# led_matrix.net
KiCad netlist of a schematic drawn in EAGLE
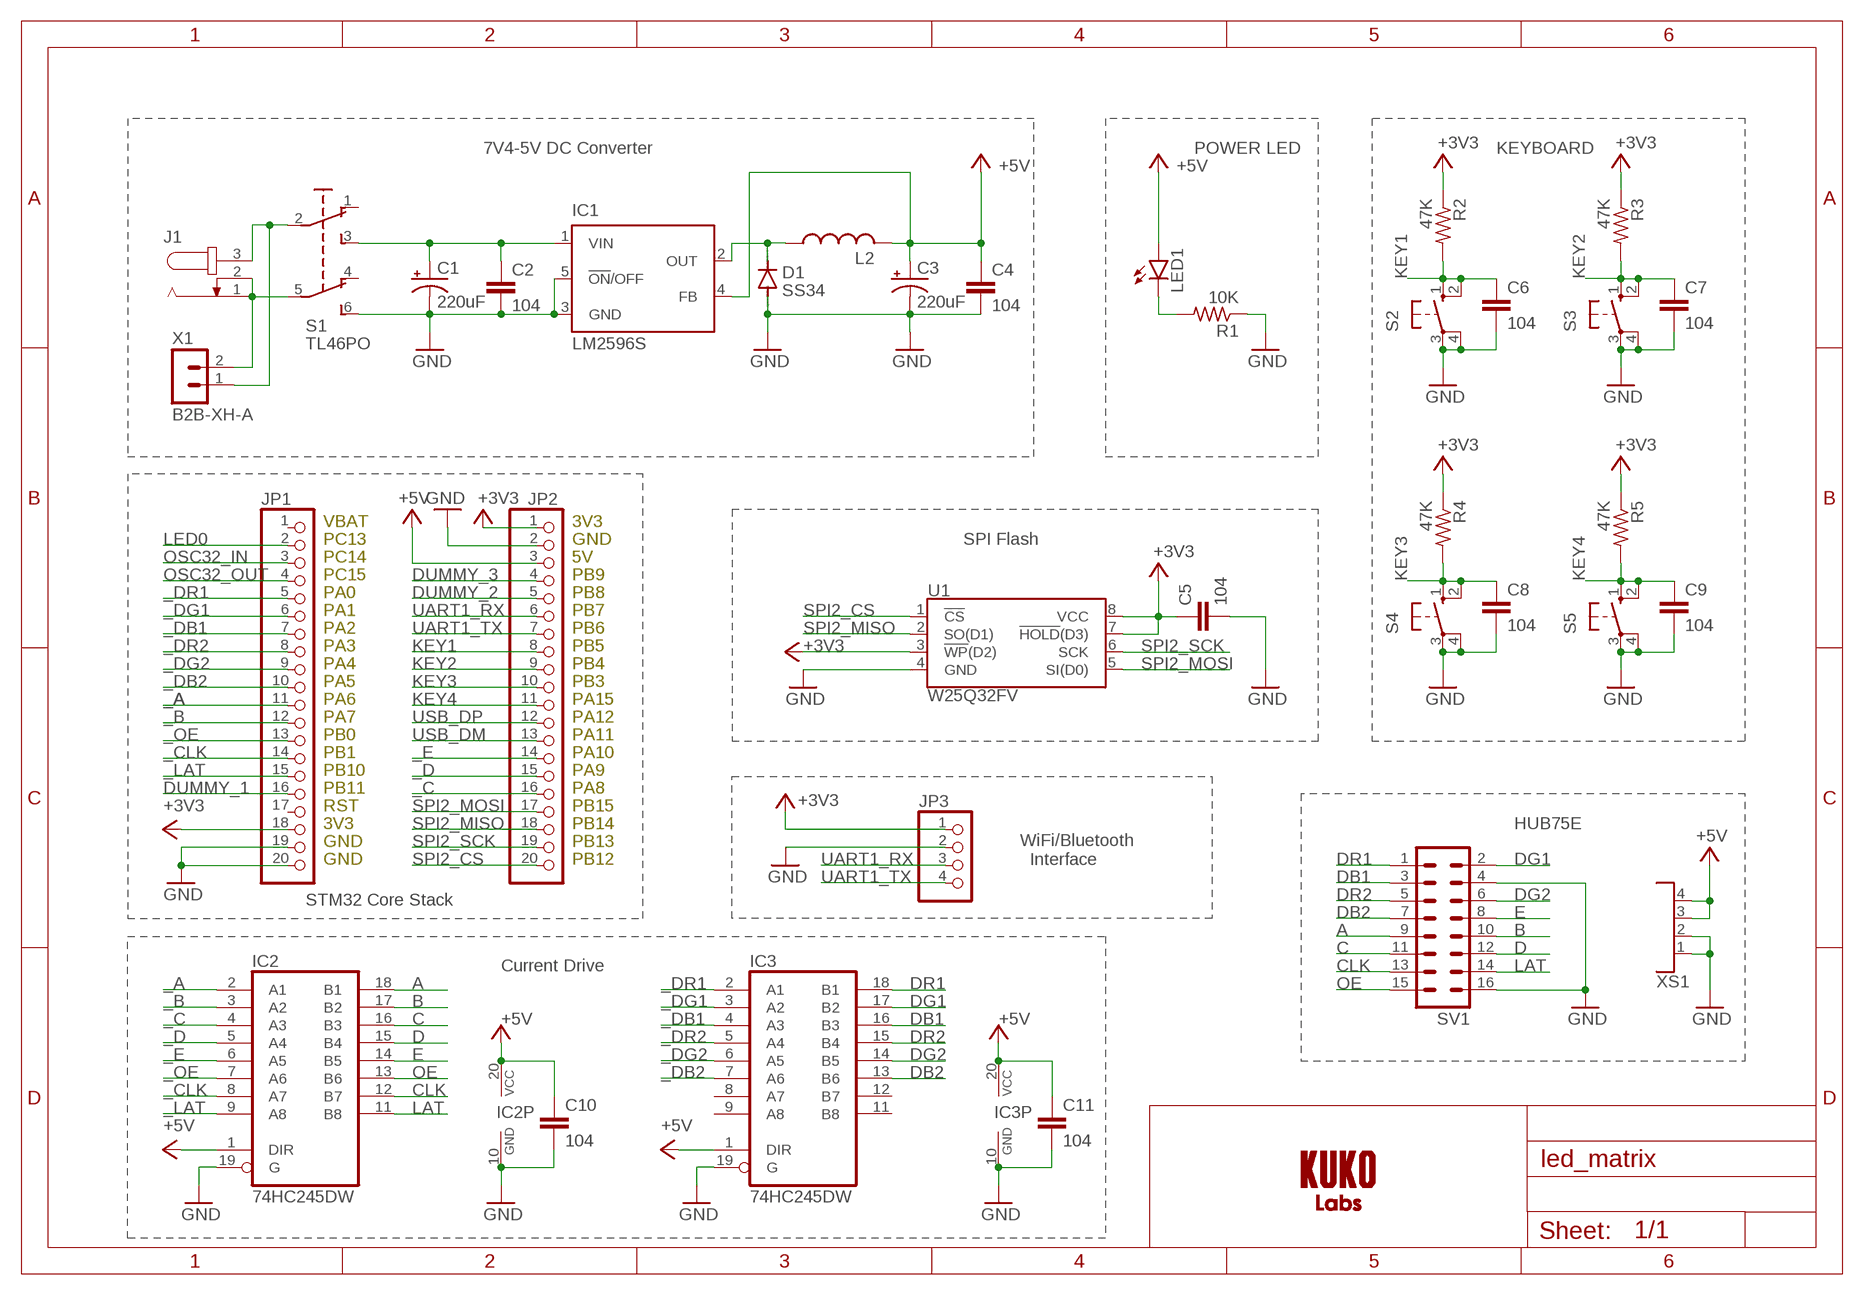
[diagram p0: schematic, sheet 1]

(export (version "E")
  (design (tool "Eeschema 10.0.6"))
  (components
    (comp (ref "C1")
      (value "220uF")
      (footprint "eagle-import:153CLV-0605")
      (libsource (lib "eagle-import") (part "CPOL-US153CLV-0605"))
    )
    (comp (ref "C2")
      (value "104")
      (footprint "eagle-import:C0805")
      (libsource (lib "eagle-import") (part "C-EUC0805"))
    )
    (comp (ref "C3")
      (value "220uF")
      (footprint "eagle-import:153CLV-0605")
      (libsource (lib "eagle-import") (part "CPOL-US153CLV-0605"))
    )
    (comp (ref "C4")
      (value "104")
      (footprint "eagle-import:C0805")
      (libsource (lib "eagle-import") (part "C-EUC0805"))
    )
    (comp (ref "C5")
      (value "104")
      (footprint "eagle-import:C0805")
      (libsource (lib "eagle-import") (part "C-EUC0805"))
    )
    (comp (ref "C6")
      (value "104")
      (footprint "eagle-import:C0805")
      (libsource (lib "eagle-import") (part "C-EUC0805"))
    )
    (comp (ref "C7")
      (value "104")
      (footprint "eagle-import:C0805")
      (libsource (lib "eagle-import") (part "C-EUC0805"))
    )
    (comp (ref "C8")
      (value "104")
      (footprint "eagle-import:C0805")
      (libsource (lib "eagle-import") (part "C-EUC0805"))
    )
    (comp (ref "C9")
      (value "104")
      (footprint "eagle-import:C0805")
      (libsource (lib "eagle-import") (part "C-EUC0805"))
    )
    (comp (ref "C10")
      (value "104")
      (footprint "eagle-import:C0805")
      (libsource (lib "eagle-import") (part "C-EUC0805"))
    )
    (comp (ref "C11")
      (value "104")
      (footprint "eagle-import:C0805")
      (libsource (lib "eagle-import") (part "C-EUC0805"))
    )
    (comp (ref "D1")
      (value "SS34")
      (footprint "eagle-import:DO214AC")
      (libsource (lib "eagle-import") (part "DIODE-DO214AC"))
    )
    (comp (ref "IC1")
      (value "LM2596S")
      (footprint "eagle-import:TO263-5")
      (fields (field (name "MF") "NATIONAL SEMICONDUCTOR") (field (name "MPN") "LM2596S-ADJ/NOPB"))
      (libsource (lib "eagle-import") (part "LM2596S"))
    )
    (comp (ref "IC2")
      (value "74HC245DW")
      (footprint "eagle-import:SO20W")
      (libsource (lib "eagle-import") (part "74245DWHC"))
    )
    (comp (ref "IC3")
      (value "74HC245DW")
      (footprint "eagle-import:SO20W")
      (libsource (lib "eagle-import") (part "74245DWHC"))
    )
    (comp (ref "J1")
      (value "JACK-PLUG0")
      (footprint "eagle-import:SPC4077")
      (libsource (lib "eagle-import") (part "JACK-PLUG0"))
    )
    (comp (ref "JP1")
      (value "PINHD-1X20")
      (footprint "eagle-import:1X20")
      (libsource (lib "eagle-import") (part "PINHD-1X20"))
    )
    (comp (ref "JP2")
      (value "PINHD-1X20")
      (footprint "eagle-import:1X20")
      (libsource (lib "eagle-import") (part "PINHD-1X20"))
    )
    (comp (ref "JP3")
      (value "PINHD-1X4")
      (footprint "eagle-import:1X04")
      (libsource (lib "eagle-import") (part "PINHD-1X4"))
    )
    (comp (ref "L2")
      (value "L-USL4532P")
      (footprint "eagle-import:L4532P")
      (libsource (lib "eagle-import") (part "L-USL4532P"))
    )
    (comp (ref "LED1")
      (value "LEDCHIP-LED0805")
      (footprint "eagle-import:CHIP-LED0805")
      (libsource (lib "eagle-import") (part "LEDCHIP-LED0805"))
    )
    (comp (ref "R1")
      (value "10K")
      (footprint "eagle-import:R0805")
      (libsource (lib "eagle-import") (part "R-US_R0805"))
    )
    (comp (ref "R2")
      (value "47K")
      (footprint "eagle-import:R0805")
      (libsource (lib "eagle-import") (part "R-US_R0805"))
    )
    (comp (ref "R3")
      (value "47K")
      (footprint "eagle-import:R0805")
      (libsource (lib "eagle-import") (part "R-US_R0805"))
    )
    (comp (ref "R4")
      (value "47K")
      (footprint "eagle-import:R0805")
      (libsource (lib "eagle-import") (part "R-US_R0805"))
    )
    (comp (ref "R5")
      (value "47K")
      (footprint "eagle-import:R0805")
      (libsource (lib "eagle-import") (part "R-US_R0805"))
    )
    (comp (ref "S1")
      (value "TL46PO")
      (footprint "eagle-import:TL4XPO")
      (libsource (lib "eagle-import") (part "TL46PO"))
    )
    (comp (ref "S2")
      (value "10-XX")
      (footprint "eagle-import:B3F-10XX")
      (fields (field (name "MPN") "B3F-1000"))
      (libsource (lib "eagle-import") (part "10-XX"))
    )
    (comp (ref "S3")
      (value "10-XX")
      (footprint "eagle-import:B3F-10XX")
      (fields (field (name "MPN") "B3F-1000"))
      (libsource (lib "eagle-import") (part "10-XX"))
    )
    (comp (ref "S4")
      (value "10-XX")
      (footprint "eagle-import:B3F-10XX")
      (fields (field (name "MPN") "B3F-1000"))
      (libsource (lib "eagle-import") (part "10-XX"))
    )
    (comp (ref "S5")
      (value "10-XX")
      (footprint "eagle-import:B3F-10XX")
      (fields (field (name "MPN") "B3F-1000"))
      (libsource (lib "eagle-import") (part "10-XX"))
    )
    (comp (ref "SV1")
      (value "ML16")
      (footprint "eagle-import:ML16")
      (libsource (lib "eagle-import") (part "ML16"))
    )
    (comp (ref "U$1")
      (value "LOGO")
      (footprint "eagle-import:LOGO")
      (libsource (lib "eagle-import") (part "LOGO?"))
    )
    (comp (ref "U1")
      (value "W25Q32FV")
      (footprint "eagle-import:SOIC-8")
      (libsource (lib "eagle-import") (part "W25Q32FVSS"))
    )
    (comp (ref "X1")
      (value "B2B-XH-A")
      (footprint "eagle-import:B2B-XH-A")
      (libsource (lib "eagle-import") (part "B2B-XH-A"))
    )
    (comp (ref "XS1")
      (value "C4")
      (footprint "eagle-import:NINIGI4C")
      (libsource (lib "eagle-import") (part "C4"))
    )
  )
  (nets
    (net (code "1") (name "+3V3") (class "Default")
      (node (ref "C5") (pin "1") (pinfunction "1_1") (pintype "passive"))
      (node (ref "JP1") (pin "18") (pinfunction "18_18") (pintype "passive"))
      (node (ref "JP2") (pin "1") (pinfunction "1_1") (pintype "passive"))
      (node (ref "JP3") (pin "1") (pinfunction "1_1") (pintype "passive"))
      (node (ref "R2") (pin "1") (pinfunction "1_1") (pintype "passive"))
      (node (ref "R3") (pin "1") (pinfunction "1_1") (pintype "passive"))
      (node (ref "R4") (pin "1") (pinfunction "1_1") (pintype "passive"))
      (node (ref "R5") (pin "1") (pinfunction "1_1") (pintype "passive"))
      (node (ref "U1") (pin "3") (pinfunction "~{WP}(D2)_3") (pintype "bidirectional"))
      (node (ref "U1") (pin "7") (pinfunction "~{HOLD}(D3)_7") (pintype "bidirectional"))
      (node (ref "U1") (pin "8") (pinfunction "VCC_8") (pintype "bidirectional"))
    )
    (net (code "2") (name "+5V") (class "Default")
      (node (ref "C10") (pin "1") (pinfunction "1_1") (pintype "passive"))
      (node (ref "C11") (pin "1") (pinfunction "1_1") (pintype "passive"))
      (node (ref "C3") (pin "+") (pinfunction "+_+") (pintype "passive"))
      (node (ref "C4") (pin "1") (pinfunction "1_1") (pintype "passive"))
      (node (ref "IC1") (pin "4") (pinfunction "FB_4") (pintype "input"))
      (node (ref "IC2") (pin "1") (pinfunction "DIR_1") (pintype "input"))
      (node (ref "IC2") (pin "20") (pinfunction "VCC_20") (pintype "power_in"))
      (node (ref "IC3") (pin "1") (pinfunction "DIR_1") (pintype "input"))
      (node (ref "IC3") (pin "20") (pinfunction "VCC_20") (pintype "power_in"))
      (node (ref "JP2") (pin "3") (pinfunction "3_3") (pintype "passive"))
      (node (ref "L2") (pin "2") (pinfunction "2_2") (pintype "passive"))
      (node (ref "LED1") (pin "A") (pinfunction "A_A") (pintype "passive"))
      (node (ref "XS1") (pin "3") (pinfunction "P$3_3") (pintype "bidirectional"))
      (node (ref "XS1") (pin "4") (pinfunction "P$4_4") (pintype "bidirectional"))
    )
    (net (code "3") (name "/A") (class "Default")
      (node (ref "IC2") (pin "18") (pinfunction "B1_18") (pintype "bidirectional"))
      (node (ref "SV1") (pin "9") (pinfunction "9_9") (pintype "passive"))
    )
    (net (code "4") (name "/B") (class "Default")
      (node (ref "IC2") (pin "17") (pinfunction "B2_17") (pintype "bidirectional"))
      (node (ref "SV1") (pin "10") (pinfunction "10_10") (pintype "passive"))
    )
    (net (code "5") (name "/C") (class "Default")
      (node (ref "IC2") (pin "16") (pinfunction "B3_16") (pintype "bidirectional"))
      (node (ref "SV1") (pin "11") (pinfunction "11_11") (pintype "passive"))
    )
    (net (code "6") (name "/CLK") (class "Default")
      (node (ref "IC2") (pin "12") (pinfunction "B7_12") (pintype "bidirectional"))
      (node (ref "SV1") (pin "13") (pinfunction "13_13") (pintype "passive"))
    )
    (net (code "7") (name "/D") (class "Default")
      (node (ref "IC2") (pin "15") (pinfunction "B4_15") (pintype "bidirectional"))
      (node (ref "SV1") (pin "12") (pinfunction "12_12") (pintype "passive"))
    )
    (net (code "8") (name "/DB1") (class "Default")
      (node (ref "IC3") (pin "16") (pinfunction "B3_16") (pintype "bidirectional"))
      (node (ref "SV1") (pin "3") (pinfunction "3_3") (pintype "passive"))
    )
    (net (code "9") (name "/DB2") (class "Default")
      (node (ref "IC3") (pin "13") (pinfunction "B6_13") (pintype "bidirectional"))
      (node (ref "SV1") (pin "7") (pinfunction "7_7") (pintype "passive"))
    )
    (net (code "10") (name "/DG1") (class "Default")
      (node (ref "IC3") (pin "17") (pinfunction "B2_17") (pintype "bidirectional"))
      (node (ref "SV1") (pin "2") (pinfunction "2_2") (pintype "passive"))
    )
    (net (code "11") (name "/DG2") (class "Default")
      (node (ref "IC3") (pin "14") (pinfunction "B5_14") (pintype "bidirectional"))
      (node (ref "SV1") (pin "6") (pinfunction "6_6") (pintype "passive"))
    )
    (net (code "12") (name "/DR1") (class "Default")
      (node (ref "IC3") (pin "18") (pinfunction "B1_18") (pintype "bidirectional"))
      (node (ref "SV1") (pin "1") (pinfunction "1_1") (pintype "passive"))
    )
    (net (code "13") (name "/DR2") (class "Default")
      (node (ref "IC3") (pin "15") (pinfunction "B4_15") (pintype "bidirectional"))
      (node (ref "SV1") (pin "5") (pinfunction "5_5") (pintype "passive"))
    )
    (net (code "14") (name "/DUMMY_1") (class "Default")
      (node (ref "JP1") (pin "16") (pinfunction "16_16") (pintype "passive"))
    )
    (net (code "15") (name "/DUMMY_2") (class "Default")
      (node (ref "JP2") (pin "5") (pinfunction "5_5") (pintype "passive"))
    )
    (net (code "16") (name "/DUMMY_3") (class "Default")
      (node (ref "JP2") (pin "4") (pinfunction "4_4") (pintype "passive"))
    )
    (net (code "17") (name "/E") (class "Default")
      (node (ref "IC2") (pin "14") (pinfunction "B5_14") (pintype "bidirectional"))
      (node (ref "SV1") (pin "8") (pinfunction "8_8") (pintype "passive"))
    )
    (net (code "18") (name "/KEY1") (class "Default")
      (node (ref "C6") (pin "1") (pinfunction "1_1") (pintype "passive"))
      (node (ref "JP2") (pin "8") (pinfunction "8_8") (pintype "passive"))
      (node (ref "R2") (pin "2") (pinfunction "2_2") (pintype "passive"))
      (node (ref "S2") (pin "1") (pinfunction "S_1") (pintype "passive"))
      (node (ref "S2") (pin "2") (pinfunction "S1_2") (pintype "passive"))
    )
    (net (code "19") (name "/KEY2") (class "Default")
      (node (ref "C7") (pin "1") (pinfunction "1_1") (pintype "passive"))
      (node (ref "JP2") (pin "9") (pinfunction "9_9") (pintype "passive"))
      (node (ref "R3") (pin "2") (pinfunction "2_2") (pintype "passive"))
      (node (ref "S3") (pin "1") (pinfunction "S_1") (pintype "passive"))
      (node (ref "S3") (pin "2") (pinfunction "S1_2") (pintype "passive"))
    )
    (net (code "20") (name "/KEY3") (class "Default")
      (node (ref "C8") (pin "1") (pinfunction "1_1") (pintype "passive"))
      (node (ref "JP2") (pin "10") (pinfunction "10_10") (pintype "passive"))
      (node (ref "R4") (pin "2") (pinfunction "2_2") (pintype "passive"))
      (node (ref "S4") (pin "1") (pinfunction "S_1") (pintype "passive"))
      (node (ref "S4") (pin "2") (pinfunction "S1_2") (pintype "passive"))
    )
    (net (code "21") (name "/KEY4") (class "Default")
      (node (ref "C9") (pin "1") (pinfunction "1_1") (pintype "passive"))
      (node (ref "JP2") (pin "11") (pinfunction "11_11") (pintype "passive"))
      (node (ref "R5") (pin "2") (pinfunction "2_2") (pintype "passive"))
      (node (ref "S5") (pin "1") (pinfunction "S_1") (pintype "passive"))
      (node (ref "S5") (pin "2") (pinfunction "S1_2") (pintype "passive"))
    )
    (net (code "22") (name "/LAT") (class "Default")
      (node (ref "IC2") (pin "11") (pinfunction "B8_11") (pintype "bidirectional"))
      (node (ref "SV1") (pin "14") (pinfunction "14_14") (pintype "passive"))
    )
    (net (code "23") (name "/LED0") (class "Default")
      (node (ref "JP1") (pin "2") (pinfunction "2_2") (pintype "passive"))
    )
    (net (code "24") (name "/OE") (class "Default")
      (node (ref "IC2") (pin "13") (pinfunction "B6_13") (pintype "bidirectional"))
      (node (ref "SV1") (pin "15") (pinfunction "15_15") (pintype "passive"))
    )
    (net (code "25") (name "/OSC32_IN") (class "Default")
      (node (ref "JP1") (pin "3") (pinfunction "3_3") (pintype "passive"))
    )
    (net (code "26") (name "/OSC32_OUT") (class "Default")
      (node (ref "JP1") (pin "4") (pinfunction "4_4") (pintype "passive"))
    )
    (net (code "27") (name "/SPI2_CS") (class "Default")
      (node (ref "JP2") (pin "20") (pinfunction "20_20") (pintype "passive"))
      (node (ref "U1") (pin "1") (pinfunction "~{CS}_1") (pintype "bidirectional"))
    )
    (net (code "28") (name "/SPI2_MISO") (class "Default")
      (node (ref "JP2") (pin "18") (pinfunction "18_18") (pintype "passive"))
      (node (ref "U1") (pin "2") (pinfunction "SO(D1)_2") (pintype "bidirectional"))
    )
    (net (code "29") (name "/SPI2_MOSI") (class "Default")
      (node (ref "JP2") (pin "17") (pinfunction "17_17") (pintype "passive"))
      (node (ref "U1") (pin "5") (pinfunction "SI(D0)_5") (pintype "bidirectional"))
    )
    (net (code "30") (name "/SPI2_SCK") (class "Default")
      (node (ref "JP2") (pin "19") (pinfunction "19_19") (pintype "passive"))
      (node (ref "U1") (pin "6") (pinfunction "SCK_6") (pintype "bidirectional"))
    )
    (net (code "31") (name "/UART1_RX") (class "Default")
      (node (ref "JP2") (pin "6") (pinfunction "6_6") (pintype "passive"))
      (node (ref "JP3") (pin "3") (pinfunction "3_3") (pintype "passive"))
    )
    (net (code "32") (name "/UART1_TX") (class "Default")
      (node (ref "JP2") (pin "7") (pinfunction "7_7") (pintype "passive"))
      (node (ref "JP3") (pin "4") (pinfunction "4_4") (pintype "passive"))
    )
    (net (code "33") (name "/USB_DM") (class "Default")
      (node (ref "JP2") (pin "13") (pinfunction "13_13") (pintype "passive"))
    )
    (net (code "34") (name "/USB_DP") (class "Default")
      (node (ref "JP2") (pin "12") (pinfunction "12_12") (pintype "passive"))
    )
    (net (code "35") (name "/_A") (class "Default")
      (node (ref "IC2") (pin "2") (pinfunction "A1_2") (pintype "bidirectional"))
      (node (ref "JP1") (pin "11") (pinfunction "11_11") (pintype "passive"))
    )
    (net (code "36") (name "/_B") (class "Default")
      (node (ref "IC2") (pin "3") (pinfunction "A2_3") (pintype "bidirectional"))
      (node (ref "JP1") (pin "12") (pinfunction "12_12") (pintype "passive"))
    )
    (net (code "37") (name "/_C") (class "Default")
      (node (ref "IC2") (pin "4") (pinfunction "A3_4") (pintype "bidirectional"))
      (node (ref "JP2") (pin "16") (pinfunction "16_16") (pintype "passive"))
    )
    (net (code "38") (name "/_CLK") (class "Default")
      (node (ref "IC2") (pin "8") (pinfunction "A7_8") (pintype "bidirectional"))
      (node (ref "JP1") (pin "14") (pinfunction "14_14") (pintype "passive"))
    )
    (net (code "39") (name "/_D") (class "Default")
      (node (ref "IC2") (pin "5") (pinfunction "A4_5") (pintype "bidirectional"))
      (node (ref "JP2") (pin "15") (pinfunction "15_15") (pintype "passive"))
    )
    (net (code "40") (name "/_DB1") (class "Default")
      (node (ref "IC3") (pin "4") (pinfunction "A3_4") (pintype "bidirectional"))
      (node (ref "JP1") (pin "7") (pinfunction "7_7") (pintype "passive"))
    )
    (net (code "41") (name "/_DB2") (class "Default")
      (node (ref "IC3") (pin "7") (pinfunction "A6_7") (pintype "bidirectional"))
      (node (ref "JP1") (pin "10") (pinfunction "10_10") (pintype "passive"))
    )
    (net (code "42") (name "/_DG1") (class "Default")
      (node (ref "IC3") (pin "3") (pinfunction "A2_3") (pintype "bidirectional"))
      (node (ref "JP1") (pin "6") (pinfunction "6_6") (pintype "passive"))
    )
    (net (code "43") (name "/_DG2") (class "Default")
      (node (ref "IC3") (pin "6") (pinfunction "A5_6") (pintype "bidirectional"))
      (node (ref "JP1") (pin "9") (pinfunction "9_9") (pintype "passive"))
    )
    (net (code "44") (name "/_DR1") (class "Default")
      (node (ref "IC3") (pin "2") (pinfunction "A1_2") (pintype "bidirectional"))
      (node (ref "JP1") (pin "5") (pinfunction "5_5") (pintype "passive"))
    )
    (net (code "45") (name "/_DR2") (class "Default")
      (node (ref "IC3") (pin "5") (pinfunction "A4_5") (pintype "bidirectional"))
      (node (ref "JP1") (pin "8") (pinfunction "8_8") (pintype "passive"))
    )
    (net (code "46") (name "/_E") (class "Default")
      (node (ref "IC2") (pin "6") (pinfunction "A5_6") (pintype "bidirectional"))
      (node (ref "JP2") (pin "14") (pinfunction "14_14") (pintype "passive"))
    )
    (net (code "47") (name "/_LAT") (class "Default")
      (node (ref "IC2") (pin "9") (pinfunction "A8_9") (pintype "bidirectional"))
      (node (ref "JP1") (pin "15") (pinfunction "15_15") (pintype "passive"))
    )
    (net (code "48") (name "/_OE") (class "Default")
      (node (ref "IC2") (pin "7") (pinfunction "A6_7") (pintype "bidirectional"))
      (node (ref "JP1") (pin "13") (pinfunction "13_13") (pintype "passive"))
    )
    (net (code "49") (name "GND") (class "Default")
      (node (ref "C1") (pin "-") (pinfunction "-_-") (pintype "passive"))
      (node (ref "C10") (pin "2") (pinfunction "2_2") (pintype "passive"))
      (node (ref "C11") (pin "2") (pinfunction "2_2") (pintype "passive"))
      (node (ref "C2") (pin "2") (pinfunction "2_2") (pintype "passive"))
      (node (ref "C3") (pin "-") (pinfunction "-_-") (pintype "passive"))
      (node (ref "C4") (pin "2") (pinfunction "2_2") (pintype "passive"))
      (node (ref "C5") (pin "2") (pinfunction "2_2") (pintype "passive"))
      (node (ref "C6") (pin "2") (pinfunction "2_2") (pintype "passive"))
      (node (ref "C7") (pin "2") (pinfunction "2_2") (pintype "passive"))
      (node (ref "C8") (pin "2") (pinfunction "2_2") (pintype "passive"))
      (node (ref "C9") (pin "2") (pinfunction "2_2") (pintype "passive"))
      (node (ref "D1") (pin "A") (pinfunction "A_A") (pintype "passive"))
      (node (ref "IC1") (pin "3") (pinfunction "GND_3") (pintype "power_in"))
      (node (ref "IC1") (pin "5") (pinfunction "~{ON}/OFF_5") (pintype "input"))
      (node (ref "IC2") (pin "10") (pinfunction "GND_10") (pintype "power_in"))
      (node (ref "IC2") (pin "19") (pinfunction "G_19") (pintype "input"))
      (node (ref "IC3") (pin "10") (pinfunction "GND_10") (pintype "power_in"))
      (node (ref "IC3") (pin "19") (pinfunction "G_19") (pintype "input"))
      (node (ref "JP1") (pin "19") (pinfunction "19_19") (pintype "passive"))
      (node (ref "JP1") (pin "20") (pinfunction "20_20") (pintype "passive"))
      (node (ref "JP2") (pin "2") (pinfunction "2_2") (pintype "passive"))
      (node (ref "JP3") (pin "2") (pinfunction "2_2") (pintype "passive"))
      (node (ref "R1") (pin "1") (pinfunction "1_1") (pintype "passive"))
      (node (ref "S1") (pin "6") (pinfunction "S1_6") (pintype "passive"))
      (node (ref "S2") (pin "3") (pinfunction "P_3") (pintype "passive"))
      (node (ref "S2") (pin "4") (pinfunction "P1_4") (pintype "passive"))
      (node (ref "S3") (pin "3") (pinfunction "P_3") (pintype "passive"))
      (node (ref "S3") (pin "4") (pinfunction "P1_4") (pintype "passive"))
      (node (ref "S4") (pin "3") (pinfunction "P_3") (pintype "passive"))
      (node (ref "S4") (pin "4") (pinfunction "P1_4") (pintype "passive"))
      (node (ref "S5") (pin "3") (pinfunction "P_3") (pintype "passive"))
      (node (ref "S5") (pin "4") (pinfunction "P1_4") (pintype "passive"))
      (node (ref "SV1") (pin "16") (pinfunction "16_16") (pintype "passive"))
      (node (ref "SV1") (pin "4") (pinfunction "4_4") (pintype "passive"))
      (node (ref "U1") (pin "4") (pinfunction "GND_4") (pintype "bidirectional"))
      (node (ref "XS1") (pin "1") (pinfunction "P$1_1") (pintype "bidirectional"))
      (node (ref "XS1") (pin "2") (pinfunction "P$2_2") (pintype "bidirectional"))
    )
    (net (code "50") (name "Net-(IC1-OUT)") (class "Default")
      (node (ref "D1") (pin "C") (pinfunction "C_C") (pintype "passive"))
      (node (ref "IC1") (pin "2") (pinfunction "OUT_2") (pintype "output"))
      (node (ref "L2") (pin "1") (pinfunction "1_1") (pintype "passive"))
    )
    (net (code "51") (name "Net-(IC1-VIN)") (class "Default")
      (node (ref "C1") (pin "+") (pinfunction "+_+") (pintype "passive"))
      (node (ref "C2") (pin "1") (pinfunction "1_1") (pintype "passive"))
      (node (ref "IC1") (pin "1") (pinfunction "VIN_1") (pintype "input"))
      (node (ref "S1") (pin "3") (pinfunction "S_3") (pintype "passive"))
    )
    (net (code "52") (name "Net-(LED1-PadC)") (class "Default")
      (node (ref "LED1") (pin "C") (pinfunction "C_C") (pintype "passive"))
      (node (ref "R1") (pin "2") (pinfunction "2_2") (pintype "passive"))
    )
    (net (code "53") (name "Net-(S1-P)") (class "Default")
      (node (ref "J1") (pin "3") (pinfunction "3_3") (pintype "passive"))
      (node (ref "S1") (pin "2") (pinfunction "P_2") (pintype "passive"))
      (node (ref "X1") (pin "1") (pinfunction "1_1") (pintype "passive"))
    )
    (net (code "54") (name "Net-(S1-P1)") (class "Default")
      (node (ref "J1") (pin "1") (pinfunction "1_1") (pintype "passive"))
      (node (ref "J1") (pin "2") (pinfunction "2_2") (pintype "passive"))
      (node (ref "S1") (pin "5") (pinfunction "P1_5") (pintype "passive"))
      (node (ref "X1") (pin "2") (pinfunction "2_2") (pintype "passive"))
    )
    (net (code "55") (name "unconnected-(IC3A-A7-Pad8)") (class "Default")
      (node (ref "IC3") (pin "8") (pinfunction "A7_8") (pintype "bidirectional"))
    )
    (net (code "56") (name "unconnected-(IC3A-A8-Pad9)") (class "Default")
      (node (ref "IC3") (pin "9") (pinfunction "A8_9") (pintype "bidirectional"))
    )
    (net (code "57") (name "unconnected-(IC3A-B7-Pad12)") (class "Default")
      (node (ref "IC3") (pin "12") (pinfunction "B7_12") (pintype "bidirectional"))
    )
    (net (code "58") (name "unconnected-(IC3A-B8-Pad11)") (class "Default")
      (node (ref "IC3") (pin "11") (pinfunction "B8_11") (pintype "bidirectional"))
    )
    (net (code "59") (name "unconnected-(JP1-Pad1)") (class "Default")
      (node (ref "JP1") (pin "1") (pinfunction "1_1") (pintype "passive"))
    )
    (net (code "60") (name "unconnected-(JP1-Pad17)") (class "Default")
      (node (ref "JP1") (pin "17") (pinfunction "17_17") (pintype "passive"))
    )
    (net (code "61") (name "unconnected-(S1-O-Pad1)") (class "Default")
      (node (ref "S1") (pin "1") (pinfunction "O_1") (pintype "passive"))
    )
    (net (code "62") (name "unconnected-(S1-O1-Pad4)") (class "Default")
      (node (ref "S1") (pin "4") (pinfunction "O1_4") (pintype "passive"))
    )
  )
)
